# RF.net
KiCad netlist of a schematic drawn in Altium Designer
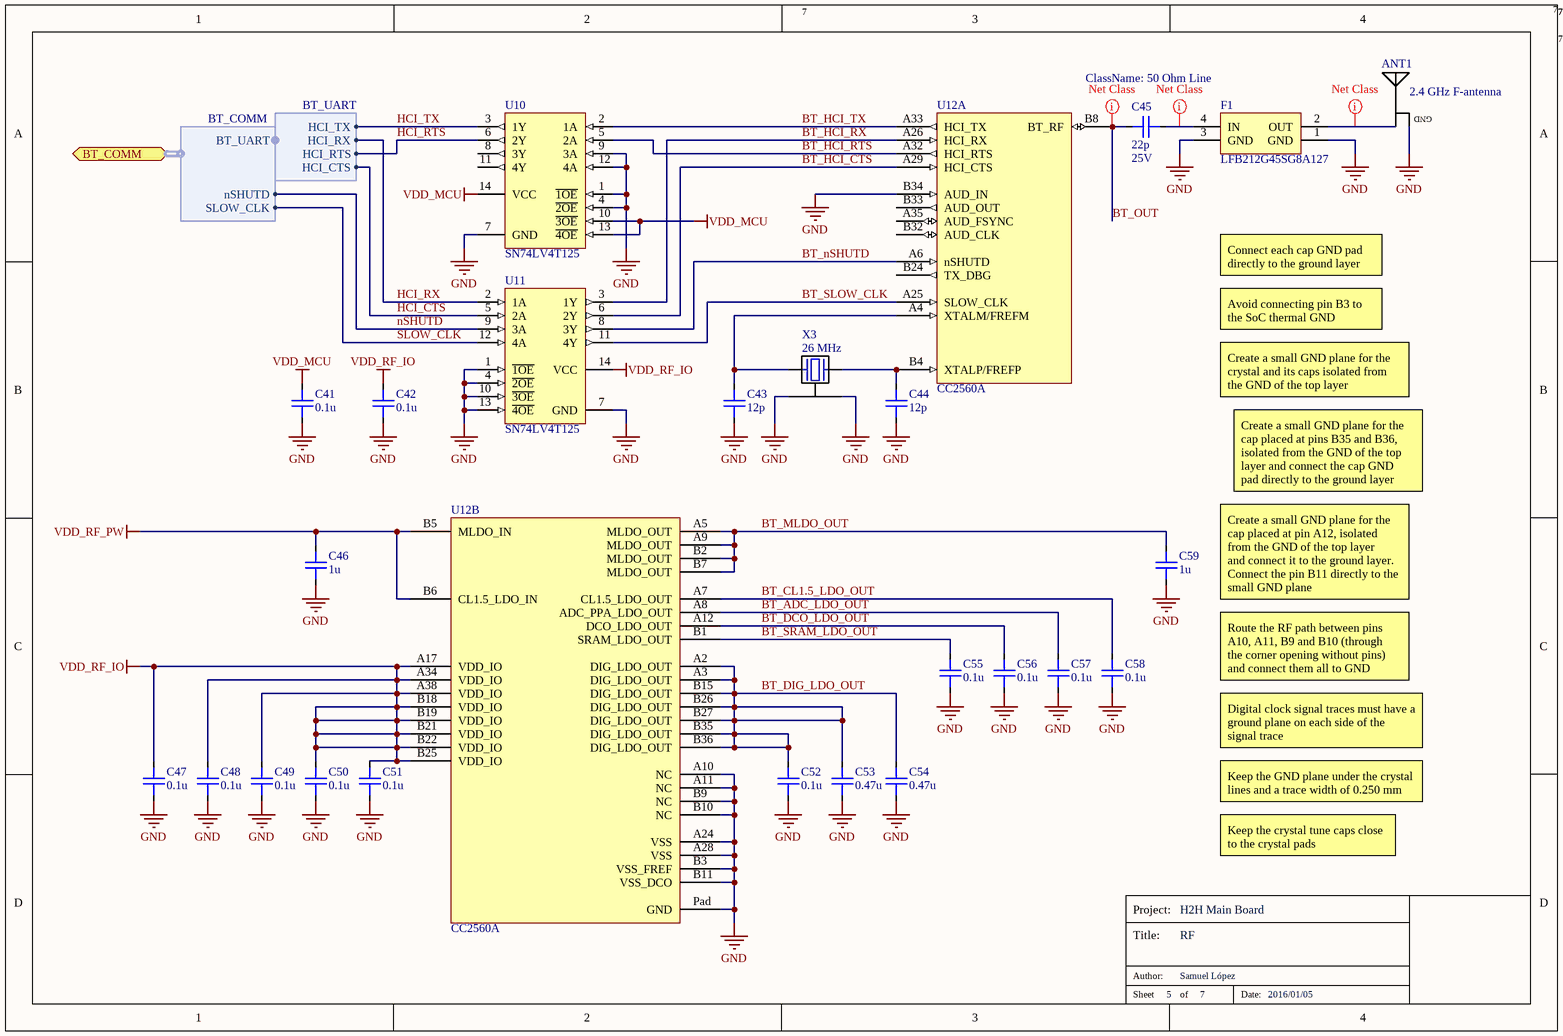
[diagram p0: RF.SchDoc]

(export (version "E")
  (design (tool "Eeschema 10.0.6"))
  (components
    (comp (ref "ANT1")
      (value "2.4 GHz F-antenna")
      (footprint "Antenna Inverted F 2.4 GHz")
      (description "Antenna - Inverted F 2.4 GHz")
      (libsource (lib "H2H") (part "ANT 2.4 GHz"))
    )
    (comp (ref "C41")
      (value "0.1u")
      (footprint "C0603")
      (description "Capacitor")
      (libsource (lib "Misc") (part "Capacitor"))
    )
    (comp (ref "C42")
      (value "0.1u")
      (footprint "C0603")
      (description "Capacitor")
      (libsource (lib "Misc") (part "Capacitor"))
    )
    (comp (ref "C43")
      (value "12p")
      (footprint "C0402")
      (description "Capacitor")
      (libsource (lib "Misc") (part "Capacitor"))
    )
    (comp (ref "C44")
      (value "12p")
      (footprint "C0402")
      (description "Capacitor")
      (libsource (lib "Misc") (part "Capacitor"))
    )
    (comp (ref "C45")
      (value "22p")
      (footprint "C0402")
      (description "Capacitor")
      (fields (field (name "RATED VOLTAGE") "25V"))
      (libsource (lib "Misc") (part "Capacitor"))
    )
    (comp (ref "C46")
      (value "1u")
      (footprint "C0402")
      (description "Capacitor")
      (libsource (lib "Misc") (part "Capacitor"))
    )
    (comp (ref "C47")
      (value "0.1u")
      (footprint "C0402")
      (description "Capacitor")
      (libsource (lib "Misc") (part "Capacitor"))
    )
    (comp (ref "C48")
      (value "0.1u")
      (footprint "C0402")
      (description "Capacitor")
      (libsource (lib "Misc") (part "Capacitor"))
    )
    (comp (ref "C49")
      (value "0.1u")
      (footprint "C0402")
      (description "Capacitor")
      (libsource (lib "Misc") (part "Capacitor"))
    )
    (comp (ref "C50")
      (value "0.1u")
      (footprint "C0402")
      (description "Capacitor")
      (libsource (lib "Misc") (part "Capacitor"))
    )
    (comp (ref "C51")
      (value "0.1u")
      (footprint "C0402")
      (description "Capacitor")
      (libsource (lib "Misc") (part "Capacitor"))
    )
    (comp (ref "C52")
      (value "0.1u")
      (footprint "C0402")
      (description "Capacitor")
      (libsource (lib "Misc") (part "Capacitor"))
    )
    (comp (ref "C53")
      (value "0.47u")
      (footprint "C0402")
      (description "Capacitor")
      (libsource (lib "Misc") (part "Capacitor"))
    )
    (comp (ref "C54")
      (value "0.47u")
      (footprint "C0402")
      (description "Capacitor")
      (libsource (lib "Misc") (part "Capacitor"))
    )
    (comp (ref "C55")
      (value "0.1u")
      (footprint "C0402")
      (description "Capacitor")
      (libsource (lib "Misc") (part "Capacitor"))
    )
    (comp (ref "C56")
      (value "0.1u")
      (footprint "C0402")
      (description "Capacitor")
      (libsource (lib "Misc") (part "Capacitor"))
    )
    (comp (ref "C57")
      (value "0.1u")
      (footprint "C0402")
      (description "Capacitor")
      (libsource (lib "Misc") (part "Capacitor"))
    )
    (comp (ref "C58")
      (value "0.1u")
      (footprint "C0402")
      (description "Capacitor")
      (libsource (lib "Misc") (part "Capacitor"))
    )
    (comp (ref "C59")
      (value "1u")
      (footprint "C0402")
      (description "Capacitor")
      (libsource (lib "Misc") (part "Capacitor"))
    )
    (comp (ref "F1")
      (value "LFB212G45SG8A127")
      (footprint "LFB212G45SG8A127")
      (description "Filter - RF 2.4 GHz")
      (libsource (lib "H2H") (part "LFB212G45SG8A127"))
    )
    (comp (ref "U10")
      (value "SN74LV4T125")
      (footprint "SN74LV4T125")
      (description "IC - Voltage Level Translator")
      (libsource (lib "") (part "SN74LV4T125_1"))
    )
    (comp (ref "U11")
      (value "SN74LV4T125")
      (footprint "SN74LV4T125")
      (description "IC - Voltage Level Translator")
      (libsource (lib "H2H") (part "SN74LV4T125"))
    )
    (comp (ref "U12")
      (value "CC2560A")
      (footprint "CC256x")
      (description "IC - Bluetooth 4.0 controller (BR/EDR)")
      (libsource (lib "H2H") (part "CC2560A"))
    )
    (comp (ref "X3")
      (value "NX2016SA")
      (footprint "NX2016SA")
      (description "Crystal - 26 MHz")
      (fields (field (name "FREQUENCY") "26 MHz"))
      (libsource (lib "H2H") (part "NX2016SA"))
    )
  )
  (nets
    (net (code "2") (name "/BT_ADC_LDO_OUT") (class "Default")
      (node (ref "C57") (pin "2") (pinfunction "2_2") (pintype "passive"))
      (node (ref "U12") (pin "A8") (pinfunction "ADC_PPA_LDO_OUT_A8") (pintype "power_in"))
    )
    (net (code "3") (name "/BT_CL1.5_LDO_OUT") (class "Default")
      (node (ref "C58") (pin "2") (pinfunction "2_2") (pintype "passive"))
      (node (ref "U12") (pin "A7") (pinfunction "CL1.5_LDO_OUT_A7") (pintype "power_in"))
    )
    (net (code "4") (name "/BT_DCO_LDO_OUT") (class "Default")
      (node (ref "C56") (pin "2") (pinfunction "2_2") (pintype "passive"))
      (node (ref "U12") (pin "A12") (pinfunction "DCO_LDO_OUT_A12") (pintype "power_in"))
    )
    (net (code "5") (name "/BT_DIG_LDO_OUT") (class "Default")
      (node (ref "C52") (pin "2") (pinfunction "2_2") (pintype "passive"))
      (node (ref "C53") (pin "2") (pinfunction "2_2") (pintype "passive"))
      (node (ref "C54") (pin "2") (pinfunction "2_2") (pintype "passive"))
      (node (ref "U12") (pin "A2") (pinfunction "DIG_LDO_OUT_A2") (pintype "power_in"))
      (node (ref "U12") (pin "A3") (pinfunction "DIG_LDO_OUT_A3") (pintype "power_in"))
      (node (ref "U12") (pin "B15") (pinfunction "DIG_LDO_OUT_B15") (pintype "power_in"))
      (node (ref "U12") (pin "B26") (pinfunction "DIG_LDO_OUT_B26") (pintype "power_in"))
      (node (ref "U12") (pin "B27") (pinfunction "DIG_LDO_OUT_B27") (pintype "power_in"))
      (node (ref "U12") (pin "B35") (pinfunction "DIG_LDO_OUT_B35") (pintype "power_in"))
      (node (ref "U12") (pin "B36") (pinfunction "DIG_LDO_OUT_B36") (pintype "power_in"))
    )
    (net (code "6") (name "/BT_HCI_CTS") (class "Default")
      (node (ref "U11") (pin "6") (pinfunction "2Y_6") (pintype "output"))
      (node (ref "U12") (pin "A29") (pinfunction "HCI_CTS_A29") (pintype "input"))
    )
    (net (code "7") (name "/BT_HCI_RTS") (class "Default")
      (node (ref "U10") (pin "5") (pinfunction "2A_5") (pintype "input"))
      (node (ref "U12") (pin "A32") (pinfunction "HCI_RTS_A32") (pintype "output"))
    )
    (net (code "8") (name "/BT_HCI_RX") (class "Default")
      (node (ref "U11") (pin "3") (pinfunction "1Y_3") (pintype "output"))
      (node (ref "U12") (pin "A26") (pinfunction "HCI_RX_A26") (pintype "input"))
    )
    (net (code "9") (name "/BT_HCI_TX") (class "Default")
      (node (ref "U10") (pin "2") (pinfunction "1A_2") (pintype "input"))
      (node (ref "U12") (pin "A33") (pinfunction "HCI_TX_A33") (pintype "output"))
    )
    (net (code "10") (name "/BT_MLDO_OUT") (class "Default")
      (node (ref "C59") (pin "2") (pinfunction "2_2") (pintype "passive"))
      (node (ref "U12") (pin "A5") (pinfunction "MLDO_OUT_A5") (pintype "power_in"))
      (node (ref "U12") (pin "A9") (pinfunction "MLDO_OUT_A9") (pintype "power_in"))
      (node (ref "U12") (pin "B2") (pinfunction "MLDO_OUT_B2") (pintype "power_in"))
      (node (ref "U12") (pin "B7") (pinfunction "MLDO_OUT_B7") (pintype "power_in"))
    )
    (net (code "11") (name "/BT_OUT") (class "Default")
      (node (ref "C45") (pin "1") (pinfunction "1_1") (pintype "passive"))
      (node (ref "U12") (pin "B8") (pinfunction "BT_RF_B8") (pintype "bidirectional"))
    )
    (net (code "12") (name "/BT_SLOW_CLK") (class "Default")
      (node (ref "U11") (pin "11") (pinfunction "4Y_11") (pintype "output"))
      (node (ref "U12") (pin "A25") (pinfunction "SLOW_CLK_A25") (pintype "input"))
    )
    (net (code "13") (name "/BT_SRAM_LDO_OUT") (class "Default")
      (node (ref "C55") (pin "2") (pinfunction "2_2") (pintype "passive"))
      (node (ref "U12") (pin "B1") (pinfunction "SRAM_LDO_OUT_B1") (pintype "power_in"))
    )
    (net (code "14") (name "/BT_nSHUTD") (class "Default")
      (node (ref "U11") (pin "8") (pinfunction "3Y_8") (pintype "output"))
      (node (ref "U12") (pin "A6") (pinfunction "nSHUTD_A6") (pintype "input"))
    )
    (net (code "15") (name "/HCI_CTS") (class "Default")
      (node (ref "U11") (pin "5") (pinfunction "2A_5") (pintype "input"))
    )
    (net (code "16") (name "/HCI_RTS") (class "Default")
      (node (ref "U10") (pin "6") (pinfunction "2Y_6") (pintype "output"))
    )
    (net (code "17") (name "/HCI_RX") (class "Default")
      (node (ref "U11") (pin "2") (pinfunction "1A_2") (pintype "input"))
    )
    (net (code "18") (name "/HCI_TX") (class "Default")
      (node (ref "U10") (pin "3") (pinfunction "1Y_3") (pintype "output"))
    )
    (net (code "19") (name "/SLOW_CLK") (class "Default")
      (node (ref "U11") (pin "12") (pinfunction "4A_12") (pintype "input"))
    )
    (net (code "20") (name "/nSHUTD") (class "Default")
      (node (ref "U11") (pin "9") (pinfunction "3A_9") (pintype "input"))
    )
    (net (code "22") (name "GND") (class "Default")
      (node (ref "ANT1") (pin "2") (pinfunction "GND_2") (pintype "passive"))
      (node (ref "C41") (pin "1") (pinfunction "1_1") (pintype "passive"))
      (node (ref "C42") (pin "1") (pinfunction "1_1") (pintype "passive"))
      (node (ref "C43") (pin "1") (pinfunction "1_1") (pintype "passive"))
      (node (ref "C44") (pin "1") (pinfunction "1_1") (pintype "passive"))
      (node (ref "C46") (pin "1") (pinfunction "1_1") (pintype "passive"))
      (node (ref "C47") (pin "1") (pinfunction "1_1") (pintype "passive"))
      (node (ref "C48") (pin "1") (pinfunction "1_1") (pintype "passive"))
      (node (ref "C49") (pin "1") (pinfunction "1_1") (pintype "passive"))
      (node (ref "C50") (pin "1") (pinfunction "1_1") (pintype "passive"))
      (node (ref "C51") (pin "1") (pinfunction "1_1") (pintype "passive"))
      (node (ref "C52") (pin "1") (pinfunction "1_1") (pintype "passive"))
      (node (ref "C53") (pin "1") (pinfunction "1_1") (pintype "passive"))
      (node (ref "C54") (pin "1") (pinfunction "1_1") (pintype "passive"))
      (node (ref "C55") (pin "1") (pinfunction "1_1") (pintype "passive"))
      (node (ref "C56") (pin "1") (pinfunction "1_1") (pintype "passive"))
      (node (ref "C57") (pin "1") (pinfunction "1_1") (pintype "passive"))
      (node (ref "C58") (pin "1") (pinfunction "1_1") (pintype "passive"))
      (node (ref "C59") (pin "1") (pinfunction "1_1") (pintype "passive"))
      (node (ref "F1") (pin "1") (pinfunction "GND_1") (pintype "power_in"))
      (node (ref "F1") (pin "3") (pinfunction "GND_3") (pintype "power_in"))
      (node (ref "U10") (pin "1") (pinfunction "~{1OE}_1") (pintype "input"))
      (node (ref "U10") (pin "12") (pinfunction "4A_12") (pintype "input"))
      (node (ref "U10") (pin "4") (pinfunction "~{2OE}_4") (pintype "input"))
      (node (ref "U10") (pin "7") (pinfunction "GND_7") (pintype "power_in"))
      (node (ref "U10") (pin "9") (pinfunction "3A_9") (pintype "input"))
      (node (ref "U11") (pin "1") (pinfunction "~{1OE}_1") (pintype "input"))
      (node (ref "U11") (pin "10") (pinfunction "~{3OE}_10") (pintype "input"))
      (node (ref "U11") (pin "13") (pinfunction "~{4OE}_13") (pintype "input"))
      (node (ref "U11") (pin "4") (pinfunction "~{2OE}_4") (pintype "input"))
      (node (ref "U11") (pin "7") (pinfunction "GND_7") (pintype "power_in"))
      (node (ref "U12") (pin "A10") (pinfunction "NC_A10") (pintype "passive"))
      (node (ref "U12") (pin "A11") (pinfunction "NC_A11") (pintype "passive"))
      (node (ref "U12") (pin "A24") (pinfunction "VSS_A24") (pintype "power_in"))
      (node (ref "U12") (pin "A28") (pinfunction "VSS_A28") (pintype "power_in"))
      (node (ref "U12") (pin "B10") (pinfunction "NC_B10") (pintype "passive"))
      (node (ref "U12") (pin "B11") (pinfunction "VSS_DCO_B11") (pintype "power_in"))
      (node (ref "U12") (pin "B3") (pinfunction "VSS_FREF_B3") (pintype "power_in"))
      (node (ref "U12") (pin "B34") (pinfunction "AUD_IN_B34") (pintype "input"))
      (node (ref "U12") (pin "B9") (pinfunction "NC_B9") (pintype "passive"))
      (node (ref "U12") (pin "Pad") (pinfunction "GND_Pad") (pintype "power_in"))
      (node (ref "X3") (pin "2") (pinfunction "2_2") (pintype "passive"))
      (node (ref "X3") (pin "4") (pinfunction "4_4") (pintype "passive"))
    )
    (net (code "23") (name "Net-(ANT1-IN)") (class "Default")
      (node (ref "ANT1") (pin "1") (pinfunction "IN_1") (pintype "passive"))
      (node (ref "F1") (pin "2") (pinfunction "OUT_2") (pintype "passive"))
    )
    (net (code "24") (name "Net-(F1-IN)") (class "Default")
      (node (ref "C45") (pin "2") (pinfunction "2_2") (pintype "passive"))
      (node (ref "F1") (pin "4") (pinfunction "IN_4") (pintype "power_in"))
    )
    (net (code "25") (name "Net-(U12A-XTALM{slash}FREFM)") (class "Default")
      (node (ref "C43") (pin "2") (pinfunction "2_2") (pintype "passive"))
      (node (ref "U12") (pin "A4") (pinfunction "XTALM/FREFM_A4") (pintype "input"))
      (node (ref "X3") (pin "1") (pinfunction "1_1") (pintype "passive"))
    )
    (net (code "26") (name "Net-(U12A-XTALP{slash}FREFP)") (class "Default")
      (node (ref "C44") (pin "2") (pinfunction "2_2") (pintype "passive"))
      (node (ref "U12") (pin "B4") (pinfunction "XTALP/FREFP_B4") (pintype "input"))
      (node (ref "X3") (pin "3") (pinfunction "3_3") (pintype "passive"))
    )
    (net (code "27") (name "VDD_MCU") (class "Default")
      (node (ref "C41") (pin "2") (pinfunction "2_2") (pintype "passive"))
      (node (ref "U10") (pin "10") (pinfunction "~{3OE}_10") (pintype "input"))
      (node (ref "U10") (pin "13") (pinfunction "~{4OE}_13") (pintype "input"))
      (node (ref "U10") (pin "14") (pinfunction "VCC_14") (pintype "power_in"))
    )
    (net (code "28") (name "VDD_RF_IO") (class "Default")
      (node (ref "C42") (pin "2") (pinfunction "2_2") (pintype "passive"))
      (node (ref "C47") (pin "2") (pinfunction "2_2") (pintype "passive"))
      (node (ref "C48") (pin "2") (pinfunction "2_2") (pintype "passive"))
      (node (ref "C49") (pin "2") (pinfunction "2_2") (pintype "passive"))
      (node (ref "C50") (pin "2") (pinfunction "2_2") (pintype "passive"))
      (node (ref "C51") (pin "2") (pinfunction "2_2") (pintype "passive"))
      (node (ref "U11") (pin "14") (pinfunction "VCC_14") (pintype "power_in"))
      (node (ref "U12") (pin "A17") (pinfunction "VDD_IO_A17") (pintype "power_in"))
      (node (ref "U12") (pin "A34") (pinfunction "VDD_IO_A34") (pintype "power_in"))
      (node (ref "U12") (pin "A38") (pinfunction "VDD_IO_A38") (pintype "power_in"))
      (node (ref "U12") (pin "B18") (pinfunction "VDD_IO_B18") (pintype "power_in"))
      (node (ref "U12") (pin "B19") (pinfunction "VDD_IO_B19") (pintype "power_in"))
      (node (ref "U12") (pin "B21") (pinfunction "VDD_IO_B21") (pintype "power_in"))
      (node (ref "U12") (pin "B22") (pinfunction "VDD_IO_B22") (pintype "power_in"))
      (node (ref "U12") (pin "B25") (pinfunction "VDD_IO_B25") (pintype "power_in"))
    )
    (net (code "29") (name "VDD_RF_PW") (class "Default")
      (node (ref "C46") (pin "2") (pinfunction "2_2") (pintype "passive"))
      (node (ref "U12") (pin "B5") (pinfunction "MLDO_IN_B5") (pintype "power_in"))
      (node (ref "U12") (pin "B6") (pinfunction "CL1.5_LDO_IN_B6") (pintype "power_in"))
    )
    (net (code "30") (name "unconnected-(U10-3Y-Pad8)") (class "Default")
      (node (ref "U10") (pin "8") (pinfunction "3Y_8") (pintype "output"))
    )
    (net (code "31") (name "unconnected-(U10-4Y-Pad11)") (class "Default")
      (node (ref "U10") (pin "11") (pinfunction "4Y_11") (pintype "output"))
    )
    (net (code "32") (name "unconnected-(U12A-AUD_CLK-PadB32)") (class "Default")
      (node (ref "U12") (pin "B32") (pinfunction "AUD_CLK_B32") (pintype "bidirectional"))
    )
    (net (code "33") (name "unconnected-(U12A-AUD_FSYNC-PadA35)") (class "Default")
      (node (ref "U12") (pin "A35") (pinfunction "AUD_FSYNC_A35") (pintype "bidirectional"))
    )
    (net (code "34") (name "unconnected-(U12A-AUD_OUT-PadB33)") (class "Default")
      (node (ref "U12") (pin "B33") (pinfunction "AUD_OUT_B33") (pintype "output"))
    )
    (net (code "35") (name "unconnected-(U12A-TX_DBG-PadB24)") (class "Default")
      (node (ref "U12") (pin "B24") (pinfunction "TX_DBG_B24") (pintype "output"))
    )
  )
)
